# rw-directish-17mm-mk-1_0.net
KiCad netlist of a schematic drawn in EAGLE
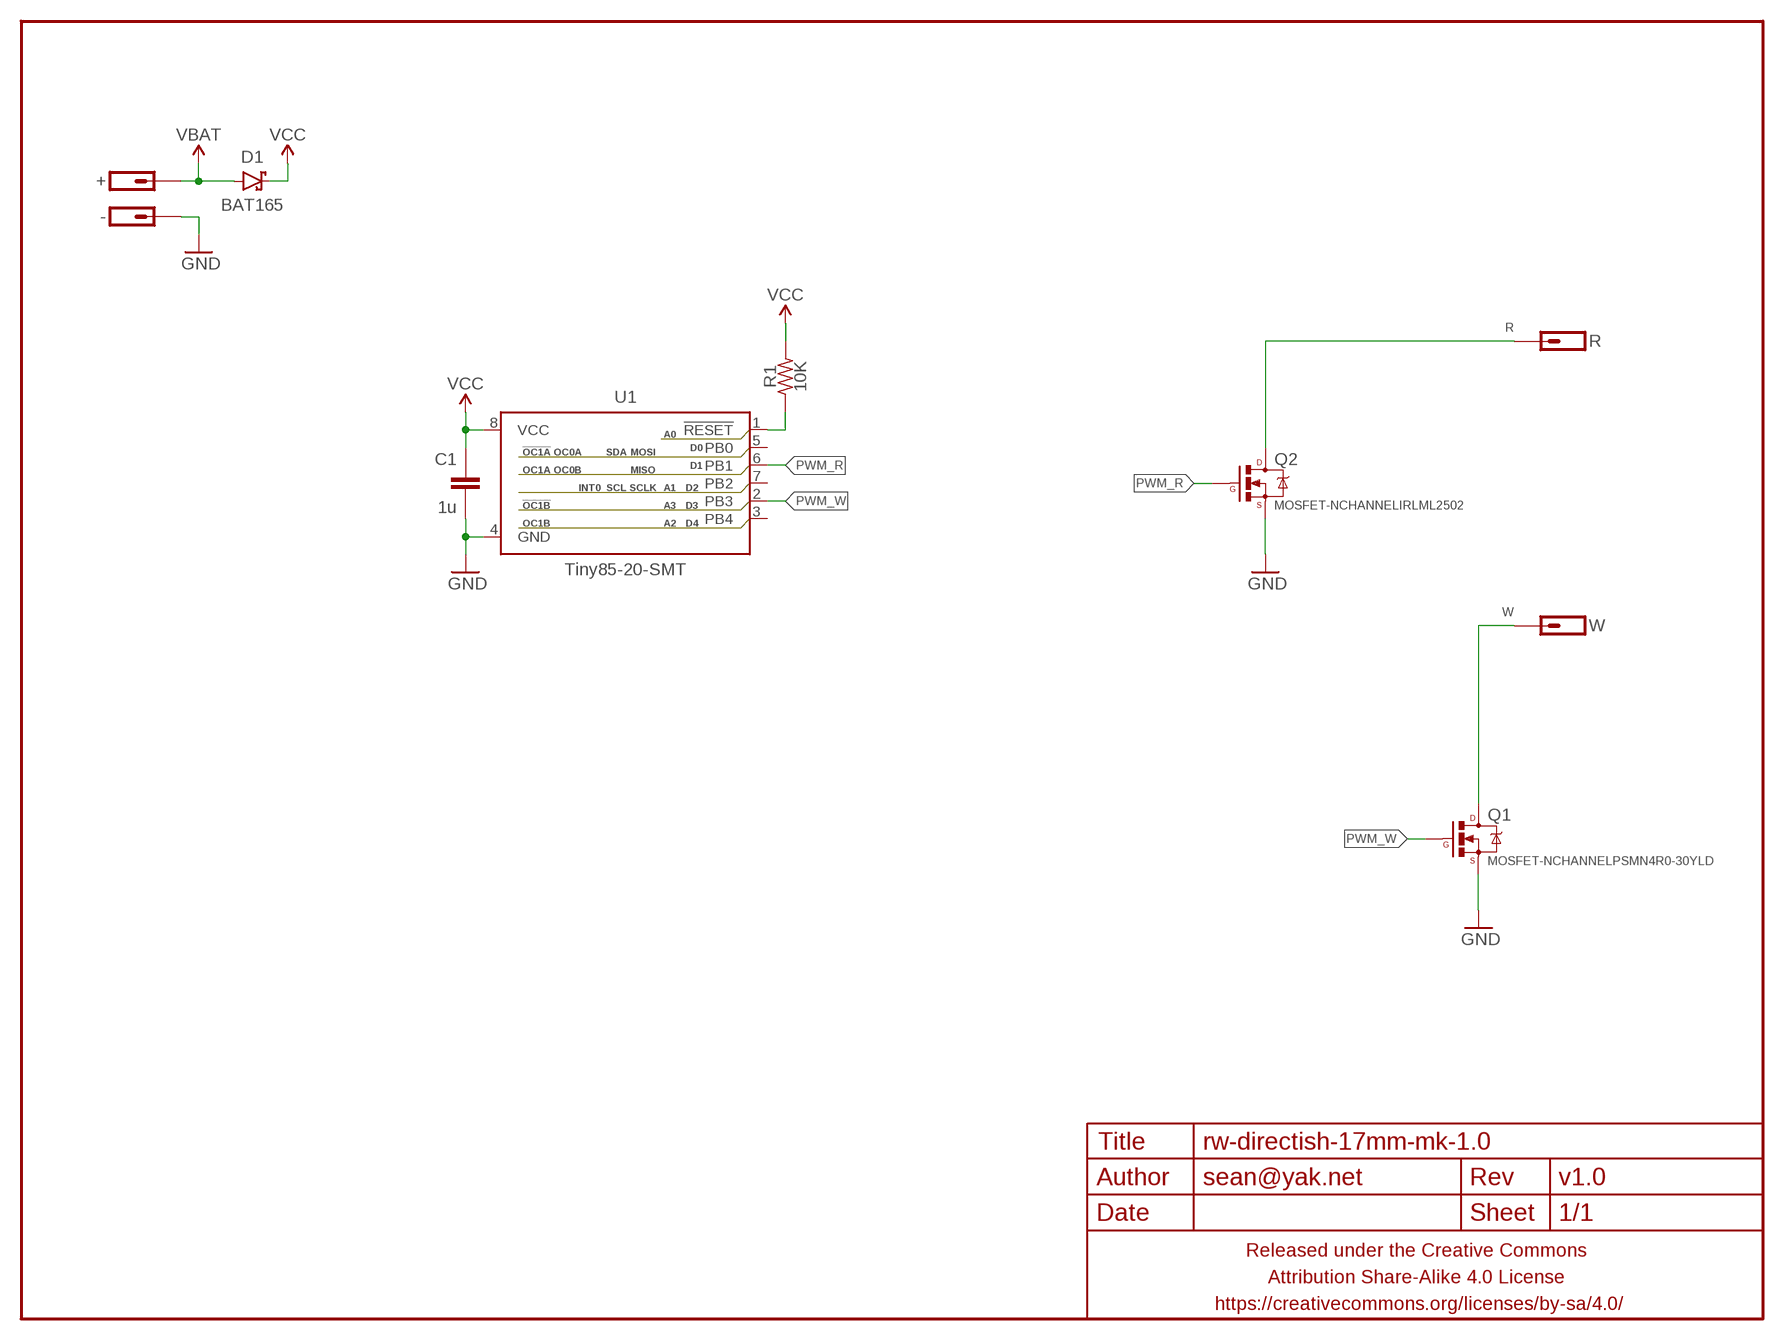
[diagram p0: schematic, sheet 1]

(export (version "E")
  (design (tool "Eeschema 10.0.6"))
  (components
    (comp (ref "+")
      (value "M01PTH-1.2MM-NS")
      (footprint "eagle-import:1X01-1.2MM-NS")
      (libsource (lib "eagle-import") (part "M01PTH-1.2MM-NS"))
    )
    (comp (ref "-")
      (value "M01NOT-A-VIA-NOPE")
      (footprint "eagle-import:1X01_NOSILK_NOSTOP")
      (libsource (lib "eagle-import") (part "M01NOT-A-VIA-NOPE"))
    )
    (comp (ref "C1")
      (value "1u")
      (footprint "eagle-import:C0402")
      (libsource (lib "eagle-import") (part "CAPACITOR-CERAMICC0402"))
    )
    (comp (ref "D1")
      (value "BAT165")
      (footprint "eagle-import:SOD323-SCHOTTKY")
      (libsource (lib "eagle-import") (part "DIODE-SCHOTTKYSOD323"))
    )
    (comp (ref "FRAME1")
      (value "FRAME-LETTERNO_PACKAGE")
      (footprint "eagle-import:DUMMY")
      (fields (field (name "DESIGNER") "sean@yak.net") (field (name "VERSION") "v1.0"))
      (libsource (lib "eagle-import") (part "FRAME-LETTERNO_PACKAGE"))
    )
    (comp (ref "Q1")
      (value "MOSFET-NCHANNELPSMN4R0-30YLD")
      (footprint "eagle-import:LFPAK56")
      (libsource (lib "eagle-import") (part "MOSFET-NCHANNELPSMN4R0-30YLD"))
    )
    (comp (ref "Q2")
      (value "MOSFET-NCHANNELIRLML2502")
      (footprint "eagle-import:SOT23")
      (libsource (lib "eagle-import") (part "MOSFET-NCHANNELIRLML2502"))
    )
    (comp (ref "R")
      (value "M01SMD-1.25MM-DIA")
      (footprint "eagle-import:1X01-SMD-1.25MM-DIA-NS")
      (libsource (lib "eagle-import") (part "M01SMD-1.25MM-DIA"))
    )
    (comp (ref "R1")
      (value "10K")
      (footprint "eagle-import:R0402")
      (libsource (lib "eagle-import") (part "RESISTORR0402"))
    )
    (comp (ref "U1")
      (value "Tiny85-20-SMT")
      (footprint "eagle-import:SO08-EIAJ")
      (libsource (lib "eagle-import") (part "ATTINY45TINY85-20-SOICW"))
    )
    (comp (ref "W")
      (value "M01SMD-1.25MM-DIA")
      (footprint "eagle-import:1X01-SMD-1.25MM-DIA-NS")
      (libsource (lib "eagle-import") (part "M01SMD-1.25MM-DIA"))
    )
  )
  (nets
    (net (code "1") (name "/R") (class "Default")
      (node (ref "Q2") (pin "3") (pinfunction "D_3") (pintype "passive"))
      (node (ref "R") (pin "P$1") (pinfunction "1_P$1") (pintype "passive"))
    )
    (net (code "2") (name "/W") (class "Default")
      (node (ref "Q1") (pin "MB@1") (pinfunction "D_MB@1") (pintype "passive"))
      (node (ref "Q1") (pin "MB@2") (pinfunction "D_MB@2") (pintype "passive"))
      (node (ref "W") (pin "P$1") (pinfunction "1_P$1") (pintype "passive"))
    )
    (net (code "3") (name "GND") (class "Default")
      (node (ref "-") (pin "P$1") (pinfunction "1_P$1") (pintype "passive"))
      (node (ref "C1") (pin "2") (pinfunction "2_2") (pintype "passive"))
      (node (ref "Q1") (pin "1") (pinfunction "S_1") (pintype "passive"))
      (node (ref "Q1") (pin "2") (pinfunction "S_2") (pintype "passive"))
      (node (ref "Q1") (pin "3") (pinfunction "S_3") (pintype "passive"))
      (node (ref "Q2") (pin "2") (pinfunction "S_2") (pintype "passive"))
      (node (ref "U1") (pin "4") (pinfunction "GND_4") (pintype "bidirectional"))
    )
    (net (code "4") (name "Net-(U1-~{RESET})") (class "Default")
      (node (ref "R1") (pin "1") (pinfunction "1_1") (pintype "passive"))
      (node (ref "U1") (pin "1") (pinfunction "~{RESET}_1") (pintype "bidirectional"))
    )
    (net (code "5") (name "PWM_R") (class "Default")
      (node (ref "Q2") (pin "1") (pinfunction "G_1") (pintype "passive"))
      (node (ref "U1") (pin "6") (pinfunction "PB1_6") (pintype "bidirectional"))
    )
    (net (code "6") (name "PWM_W") (class "Default")
      (node (ref "Q1") (pin "4") (pinfunction "G_4") (pintype "passive"))
      (node (ref "U1") (pin "2") (pinfunction "PB3_2") (pintype "bidirectional"))
    )
    (net (code "7") (name "VBAT") (class "Default")
      (node (ref "+") (pin "P$1") (pinfunction "1_P$1") (pintype "passive"))
      (node (ref "D1") (pin "A") (pinfunction "A_A") (pintype "passive"))
    )
    (net (code "8") (name "VCC") (class "Default")
      (node (ref "C1") (pin "1") (pinfunction "1_1") (pintype "passive"))
      (node (ref "D1") (pin "C") (pinfunction "C_C") (pintype "passive"))
      (node (ref "R1") (pin "2") (pinfunction "2_2") (pintype "passive"))
      (node (ref "U1") (pin "8") (pinfunction "VCC_8") (pintype "bidirectional"))
    )
    (net (code "9") (name "unconnected-(U1-PB0-Pad5)") (class "Default")
      (node (ref "U1") (pin "5") (pinfunction "PB0_5") (pintype "bidirectional"))
    )
    (net (code "10") (name "unconnected-(U1-PB2-Pad7)") (class "Default")
      (node (ref "U1") (pin "7") (pinfunction "PB2_7") (pintype "bidirectional"))
    )
    (net (code "11") (name "unconnected-(U1-PB4-Pad3)") (class "Default")
      (node (ref "U1") (pin "3") (pinfunction "PB4_3") (pintype "bidirectional"))
    )
  )
)
